# PWMExpander.net
KiCad netlist of a schematic drawn in Altium Designer
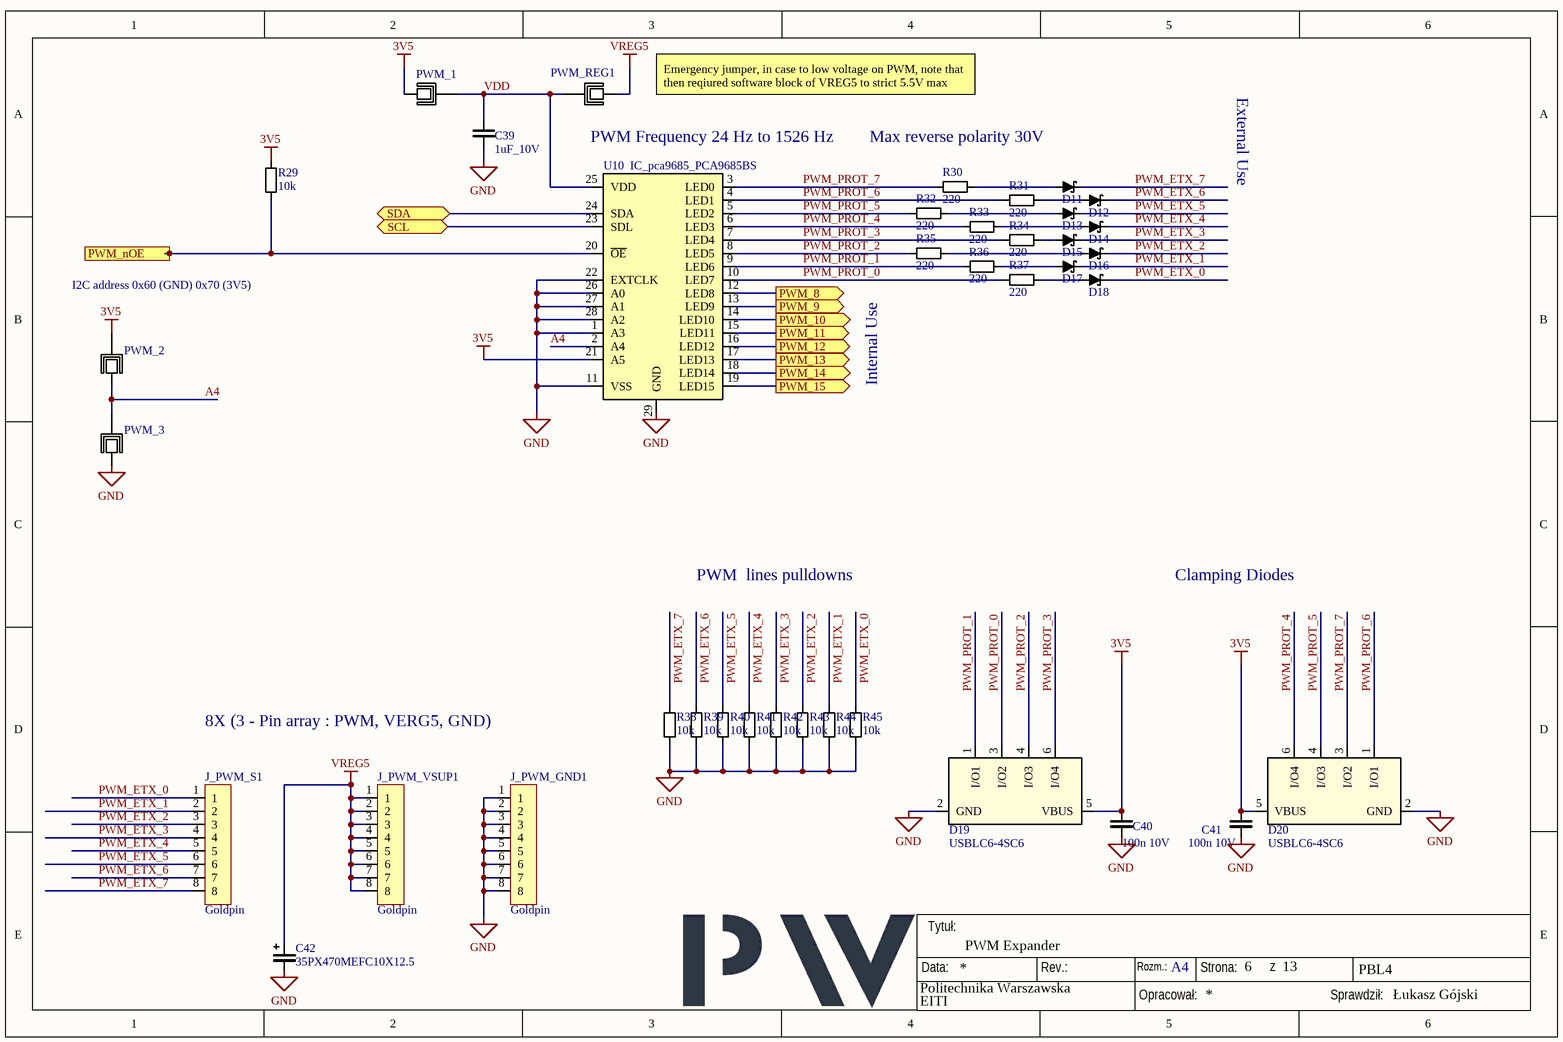
[diagram p0: PWMExpander.SchDoc]

(export (version "E")
  (design (tool "Eeschema 10.0.6"))
  (components
    (comp (ref "C39")
      (value "1uF_10V")
      (footprint "C_0603")
      (description "Ceramic capacitor")
      (fields (field (name "VOLTAGE") "10V") (field (name "TOLERANCE") "10%"))
      (libsource (lib "Common") (part "C_1uF_10V"))
    )
    (comp (ref "C40")
      (value "100n 10V")
      (footprint "C_0603")
      (description "Ceramic capacitor")
      (fields (field (name "VOLTAGE") "10V") (field (name "TOLERANCE") "10%"))
      (libsource (lib "Common") (part "C_100nF_10V"))
    )
    (comp (ref "C41")
      (value "100n 10V")
      (footprint "C_0603")
      (description "Ceramic capacitor")
      (fields (field (name "VOLTAGE") "10V") (field (name "TOLERANCE") "10%"))
      (libsource (lib "Common") (part "C_100nF_10V"))
    )
    (comp (ref "C42")
      (value "35PX470MEFC10X12.5")
      (footprint "CAP_PKPZ_10X12P5_LOW_RUB")
      (description "470 µF 35 V Aluminum Electrolytic Capacitors Radial, Can 2000 Hrs @ 105°C")
      (fields (field (name "VOLTAGE") "35V") (field (name "TOLERANCE") "20%"))
      (libsource (lib "Common") (part "C_Pol_470uF_35V"))
    )
    (comp (ref "D11")
      (value "CUS520,H3F")
      (footprint "SOD2513X115N")
      (description "Schottky Diode 200mA 30V reverse")
      (fields (field (name "POWER") "150mW"))
      (libsource (lib "Common") (part "D schottky 200mA"))
    )
    (comp (ref "D12")
      (value "CUS520,H3F")
      (footprint "SOD2513X115N")
      (description "Schottky Diode 200mA 30V reverse")
      (fields (field (name "POWER") "150mW"))
      (libsource (lib "Common") (part "D schottky 200mA"))
    )
    (comp (ref "D13")
      (value "CUS520,H3F")
      (footprint "SOD2513X115N")
      (description "Schottky Diode 200mA 30V reverse")
      (fields (field (name "POWER") "150mW"))
      (libsource (lib "Common") (part "D schottky 200mA"))
    )
    (comp (ref "D14")
      (value "CUS520,H3F")
      (footprint "SOD2513X115N")
      (description "Schottky Diode 200mA 30V reverse")
      (fields (field (name "POWER") "150mW"))
      (libsource (lib "Common") (part "D schottky 200mA"))
    )
    (comp (ref "D15")
      (value "CUS520,H3F")
      (footprint "SOD2513X115N")
      (description "Schottky Diode 200mA 30V reverse")
      (fields (field (name "POWER") "150mW"))
      (libsource (lib "Common") (part "D schottky 200mA"))
    )
    (comp (ref "D16")
      (value "CUS520,H3F")
      (footprint "SOD2513X115N")
      (description "Schottky Diode 200mA 30V reverse")
      (fields (field (name "POWER") "150mW"))
      (libsource (lib "Common") (part "D schottky 200mA"))
    )
    (comp (ref "D17")
      (value "CUS520,H3F")
      (footprint "SOD2513X115N")
      (description "Schottky Diode 200mA 30V reverse")
      (fields (field (name "POWER") "150mW"))
      (libsource (lib "Common") (part "D schottky 200mA"))
    )
    (comp (ref "D18")
      (value "CUS520,H3F")
      (footprint "SOD2513X115N")
      (description "Schottky Diode 200mA 30V reverse")
      (fields (field (name "POWER") "150mW"))
      (libsource (lib "Common") (part "D schottky 200mA"))
    )
    (comp (ref "D19")
      (value "USBLC6-4SC6")
      (footprint "SOT23-6L_STM")
      (description "Very low capacitance ESD protection")
      (fields (field (name "COPYRIGHT") "Copyright (C) 2025 Ultra Librarian. All rights reserved."))
      (libsource (lib "") (part "USBLC6-4SC6_1"))
    )
    (comp (ref "D20")
      (value "USBLC6-4SC6")
      (footprint "SOT23-6L_STM")
      (description "Very low capacitance ESD protection")
      (fields (field (name "COPYRIGHT") "Copyright (C) 2025 Ultra Librarian. All rights reserved."))
      (libsource (lib "Common") (part "USBLC6-4SC6"))
    )
    (comp (ref "J_PWM_GND1")
      (value "Goldpin")
      (footprint "goldpin8")
      (description "Goldpin Male 8")
      (libsource (lib "Common") (part "Goldpin_array_8"))
    )
    (comp (ref "J_PWM_S1")
      (value "Goldpin")
      (footprint "goldpin8")
      (description "Goldpin Male 8")
      (libsource (lib "Common") (part "Goldpin_array_8"))
    )
    (comp (ref "J_PWM_VSUP1")
      (value "Goldpin")
      (footprint "goldpin8")
      (description "Goldpin Male 8")
      (libsource (lib "Common") (part "Goldpin_array_8"))
    )
    (comp (ref "PWM_1")
      (value "JUMPER")
      (footprint "Jumper")
      (description "Jumper on traces")
      (libsource (lib "Common") (part "Jumper x2"))
    )
    (comp (ref "PWM_2")
      (value "JUMPER")
      (footprint "Jumper")
      (description "Jumper on traces")
      (libsource (lib "Common") (part "Jumper x2"))
    )
    (comp (ref "PWM_3")
      (value "JUMPER")
      (footprint "Jumper")
      (description "Jumper on traces")
      (libsource (lib "Common") (part "Jumper x2"))
    )
    (comp (ref "PWM_REG1")
      (value "JUMPER")
      (footprint "Jumper")
      (description "Jumper on traces")
      (libsource (lib "Common") (part "Jumper x2"))
    )
    (comp (ref "R29")
      (value "10k")
      (footprint "R_0603")
      (description "Resistor")
      (fields (field (name "TOLERANCE") "1%") (field (name "POWER") "100mW"))
      (libsource (lib "Common") (part "R_10k"))
    )
    (comp (ref "R30")
      (value "220")
      (footprint "R_0603")
      (description "Resistor")
      (fields (field (name "TOLERANCE") "1%") (field (name "POWER") "100mW"))
      (libsource (lib "Common") (part "R_220R"))
    )
    (comp (ref "R31")
      (value "220")
      (footprint "R_0603")
      (description "Resistor")
      (fields (field (name "TOLERANCE") "1%") (field (name "POWER") "100mW"))
      (libsource (lib "Common") (part "R_220R"))
    )
    (comp (ref "R32")
      (value "220")
      (footprint "R_0603")
      (description "Resistor")
      (fields (field (name "TOLERANCE") "1%") (field (name "POWER") "100mW"))
      (libsource (lib "Common") (part "R_220R"))
    )
    (comp (ref "R33")
      (value "220")
      (footprint "R_0603")
      (description "Resistor")
      (fields (field (name "TOLERANCE") "1%") (field (name "POWER") "100mW"))
      (libsource (lib "Common") (part "R_220R"))
    )
    (comp (ref "R34")
      (value "220")
      (footprint "R_0603")
      (description "Resistor")
      (fields (field (name "TOLERANCE") "1%") (field (name "POWER") "100mW"))
      (libsource (lib "Common") (part "R_220R"))
    )
    (comp (ref "R35")
      (value "220")
      (footprint "R_0603")
      (description "Resistor")
      (fields (field (name "TOLERANCE") "1%") (field (name "POWER") "100mW"))
      (libsource (lib "Common") (part "R_220R"))
    )
    (comp (ref "R36")
      (value "220")
      (footprint "R_0603")
      (description "Resistor")
      (fields (field (name "TOLERANCE") "1%") (field (name "POWER") "100mW"))
      (libsource (lib "Common") (part "R_220R"))
    )
    (comp (ref "R37")
      (value "220")
      (footprint "R_0603")
      (description "Resistor")
      (fields (field (name "TOLERANCE") "1%") (field (name "POWER") "100mW"))
      (libsource (lib "Common") (part "R_220R"))
    )
    (comp (ref "R38")
      (value "10k")
      (footprint "R_0603")
      (description "Resistor")
      (fields (field (name "TOLERANCE") "1%") (field (name "POWER") "100mW"))
      (libsource (lib "Common") (part "R_10k"))
    )
    (comp (ref "R39")
      (value "10k")
      (footprint "R_0603")
      (description "Resistor")
      (fields (field (name "TOLERANCE") "1%") (field (name "POWER") "100mW"))
      (libsource (lib "Common") (part "R_10k"))
    )
    (comp (ref "R40")
      (value "10k")
      (footprint "R_0603")
      (description "Resistor")
      (fields (field (name "TOLERANCE") "1%") (field (name "POWER") "100mW"))
      (libsource (lib "Common") (part "R_10k"))
    )
    (comp (ref "R41")
      (value "10k")
      (footprint "R_0603")
      (description "Resistor")
      (fields (field (name "TOLERANCE") "1%") (field (name "POWER") "100mW"))
      (libsource (lib "Common") (part "R_10k"))
    )
    (comp (ref "R42")
      (value "10k")
      (footprint "R_0603")
      (description "Resistor")
      (fields (field (name "TOLERANCE") "1%") (field (name "POWER") "100mW"))
      (libsource (lib "Common") (part "R_10k"))
    )
    (comp (ref "R43")
      (value "10k")
      (footprint "R_0603")
      (description "Resistor")
      (fields (field (name "TOLERANCE") "1%") (field (name "POWER") "100mW"))
      (libsource (lib "Common") (part "R_10k"))
    )
    (comp (ref "R44")
      (value "10k")
      (footprint "R_0603")
      (description "Resistor")
      (fields (field (name "TOLERANCE") "1%") (field (name "POWER") "100mW"))
      (libsource (lib "Common") (part "R_10k"))
    )
    (comp (ref "R45")
      (value "10k")
      (footprint "R_0603")
      (description "Resistor")
      (fields (field (name "TOLERANCE") "1%") (field (name "POWER") "100mW"))
      (libsource (lib "Common") (part "R_10k"))
    )
    (comp (ref "U10")
      (value "IC_pca9685_PCA9685BS")
      (footprint "PCA9685_SOT788-1")
      (libsource (lib "IOLib") (part "IC_pca9685_PCA9685BS"))
    )
  )
  (nets
    (net (code "1") (name "/A4") (class "Default")
      (node (ref "PWM_2") (pin "1") (pinfunction "1_1") (pintype "passive"))
      (node (ref "PWM_3") (pin "2") (pinfunction "2_2") (pintype "passive"))
      (node (ref "U10") (pin "2") (pinfunction "A4_2") (pintype "passive"))
    )
    (net (code "2") (name "/PWM_8") (class "Default")
      (node (ref "U10") (pin "12") (pinfunction "LED8_12") (pintype "passive"))
    )
    (net (code "3") (name "/PWM_9") (class "Default")
      (node (ref "U10") (pin "13") (pinfunction "LED9_13") (pintype "passive"))
    )
    (net (code "4") (name "/PWM_10") (class "Default")
      (node (ref "U10") (pin "14") (pinfunction "LED10_14") (pintype "passive"))
    )
    (net (code "5") (name "/PWM_11") (class "Default")
      (node (ref "U10") (pin "15") (pinfunction "LED11_15") (pintype "passive"))
    )
    (net (code "6") (name "/PWM_12") (class "Default")
      (node (ref "U10") (pin "16") (pinfunction "LED12_16") (pintype "passive"))
    )
    (net (code "7") (name "/PWM_13") (class "Default")
      (node (ref "U10") (pin "17") (pinfunction "LED13_17") (pintype "passive"))
    )
    (net (code "8") (name "/PWM_14") (class "Default")
      (node (ref "U10") (pin "18") (pinfunction "LED14_18") (pintype "passive"))
    )
    (net (code "9") (name "/PWM_15") (class "Default")
      (node (ref "U10") (pin "19") (pinfunction "LED15_19") (pintype "passive"))
    )
    (net (code "10") (name "/PWM_ETX_0") (class "Default")
      (node (ref "D18") (pin "K") (pinfunction "K_K") (pintype "passive"))
      (node (ref "J_PWM_S1") (pin "1") (pinfunction "1_1") (pintype "passive"))
      (node (ref "R45") (pin "2") (pinfunction "2_2") (pintype "passive"))
    )
    (net (code "11") (name "/PWM_ETX_1") (class "Default")
      (node (ref "D17") (pin "K") (pinfunction "K_K") (pintype "passive"))
      (node (ref "J_PWM_S1") (pin "2") (pinfunction "2_2") (pintype "passive"))
      (node (ref "R44") (pin "2") (pinfunction "2_2") (pintype "passive"))
    )
    (net (code "12") (name "/PWM_ETX_2") (class "Default")
      (node (ref "D16") (pin "K") (pinfunction "K_K") (pintype "passive"))
      (node (ref "J_PWM_S1") (pin "3") (pinfunction "3_3") (pintype "passive"))
      (node (ref "R43") (pin "2") (pinfunction "2_2") (pintype "passive"))
    )
    (net (code "13") (name "/PWM_ETX_3") (class "Default")
      (node (ref "D15") (pin "K") (pinfunction "K_K") (pintype "passive"))
      (node (ref "J_PWM_S1") (pin "4") (pinfunction "4_4") (pintype "passive"))
      (node (ref "R42") (pin "2") (pinfunction "2_2") (pintype "passive"))
    )
    (net (code "14") (name "/PWM_ETX_4") (class "Default")
      (node (ref "D14") (pin "K") (pinfunction "K_K") (pintype "passive"))
      (node (ref "J_PWM_S1") (pin "5") (pinfunction "5_5") (pintype "passive"))
      (node (ref "R41") (pin "2") (pinfunction "2_2") (pintype "passive"))
    )
    (net (code "15") (name "/PWM_ETX_5") (class "Default")
      (node (ref "D13") (pin "K") (pinfunction "K_K") (pintype "passive"))
      (node (ref "J_PWM_S1") (pin "6") (pinfunction "6_6") (pintype "passive"))
      (node (ref "R40") (pin "2") (pinfunction "2_2") (pintype "passive"))
    )
    (net (code "16") (name "/PWM_ETX_6") (class "Default")
      (node (ref "D12") (pin "K") (pinfunction "K_K") (pintype "passive"))
      (node (ref "J_PWM_S1") (pin "7") (pinfunction "7_7") (pintype "passive"))
      (node (ref "R39") (pin "2") (pinfunction "2_2") (pintype "passive"))
    )
    (net (code "17") (name "/PWM_ETX_7") (class "Default")
      (node (ref "D11") (pin "K") (pinfunction "K_K") (pintype "passive"))
      (node (ref "J_PWM_S1") (pin "8") (pinfunction "8_8") (pintype "passive"))
      (node (ref "R38") (pin "2") (pinfunction "2_2") (pintype "passive"))
    )
    (net (code "18") (name "/PWM_PROT_0") (class "Default")
      (node (ref "D19") (pin "3") (pinfunction "I/O2_3") (pintype "passive"))
      (node (ref "R37") (pin "1") (pinfunction "1_1") (pintype "passive"))
      (node (ref "U10") (pin "10") (pinfunction "LED7_10") (pintype "passive"))
    )
    (net (code "19") (name "/PWM_PROT_1") (class "Default")
      (node (ref "D19") (pin "1") (pinfunction "I/O1_1") (pintype "passive"))
      (node (ref "R36") (pin "1") (pinfunction "1_1") (pintype "passive"))
      (node (ref "U10") (pin "9") (pinfunction "LED6_9") (pintype "passive"))
    )
    (net (code "20") (name "/PWM_PROT_2") (class "Default")
      (node (ref "D19") (pin "4") (pinfunction "I/O3_4") (pintype "passive"))
      (node (ref "R35") (pin "1") (pinfunction "1_1") (pintype "passive"))
      (node (ref "U10") (pin "8") (pinfunction "LED5_8") (pintype "passive"))
    )
    (net (code "21") (name "/PWM_PROT_3") (class "Default")
      (node (ref "D19") (pin "6") (pinfunction "I/O4_6") (pintype "passive"))
      (node (ref "R34") (pin "1") (pinfunction "1_1") (pintype "passive"))
      (node (ref "U10") (pin "7") (pinfunction "LED4_7") (pintype "passive"))
    )
    (net (code "22") (name "/PWM_PROT_4") (class "Default")
      (node (ref "D20") (pin "6") (pinfunction "I/O4_6") (pintype "passive"))
      (node (ref "R33") (pin "1") (pinfunction "1_1") (pintype "passive"))
      (node (ref "U10") (pin "6") (pinfunction "LED3_6") (pintype "passive"))
    )
    (net (code "23") (name "/PWM_PROT_5") (class "Default")
      (node (ref "D20") (pin "4") (pinfunction "I/O3_4") (pintype "passive"))
      (node (ref "R32") (pin "1") (pinfunction "1_1") (pintype "passive"))
      (node (ref "U10") (pin "5") (pinfunction "LED2_5") (pintype "passive"))
    )
    (net (code "24") (name "/PWM_PROT_6") (class "Default")
      (node (ref "D20") (pin "1") (pinfunction "I/O1_1") (pintype "passive"))
      (node (ref "R31") (pin "1") (pinfunction "1_1") (pintype "passive"))
      (node (ref "U10") (pin "4") (pinfunction "LED1_4") (pintype "passive"))
    )
    (net (code "25") (name "/PWM_PROT_7") (class "Default")
      (node (ref "D20") (pin "3") (pinfunction "I/O2_3") (pintype "passive"))
      (node (ref "R30") (pin "1") (pinfunction "1_1") (pintype "passive"))
      (node (ref "U10") (pin "3") (pinfunction "LED0_3") (pintype "passive"))
    )
    (net (code "26") (name "/PWM_nOE") (class "Default")
      (node (ref "R29") (pin "1") (pinfunction "1_1") (pintype "passive"))
      (node (ref "U10") (pin "20") (pinfunction "~{OE}_20") (pintype "passive"))
    )
    (net (code "27") (name "/SCL") (class "Default")
      (node (ref "U10") (pin "23") (pinfunction "SDL_23") (pintype "passive"))
    )
    (net (code "28") (name "/SDA") (class "Default")
      (node (ref "U10") (pin "24") (pinfunction "SDA_24") (pintype "passive"))
    )
    (net (code "29") (name "/VDD") (class "Default")
      (node (ref "C39") (pin "2") (pinfunction "2_2") (pintype "passive"))
      (node (ref "PWM_1") (pin "2") (pinfunction "2_2") (pintype "passive"))
      (node (ref "PWM_REG1") (pin "2") (pinfunction "2_2") (pintype "passive"))
      (node (ref "U10") (pin "25") (pinfunction "VDD_25") (pintype "passive"))
    )
    (net (code "30") (name "3V5") (class "Default")
      (node (ref "C40") (pin "2") (pinfunction "2_2") (pintype "passive"))
      (node (ref "C41") (pin "2") (pinfunction "2_2") (pintype "passive"))
      (node (ref "D19") (pin "5") (pinfunction "VBUS_5") (pintype "passive"))
      (node (ref "D20") (pin "5") (pinfunction "VBUS_5") (pintype "passive"))
      (node (ref "PWM_1") (pin "1") (pinfunction "1_1") (pintype "passive"))
      (node (ref "PWM_2") (pin "2") (pinfunction "2_2") (pintype "passive"))
      (node (ref "R29") (pin "2") (pinfunction "2_2") (pintype "passive"))
      (node (ref "U10") (pin "21") (pinfunction "A5_21") (pintype "passive"))
    )
    (net (code "31") (name "GND") (class "Default")
      (node (ref "C39") (pin "1") (pinfunction "1_1") (pintype "passive"))
      (node (ref "C40") (pin "1") (pinfunction "1_1") (pintype "passive"))
      (node (ref "C41") (pin "1") (pinfunction "1_1") (pintype "passive"))
      (node (ref "C42") (pin "2") (pinfunction "2_2") (pintype "passive"))
      (node (ref "D19") (pin "2") (pinfunction "GND_2") (pintype "passive"))
      (node (ref "D20") (pin "2") (pinfunction "GND_2") (pintype "passive"))
      (node (ref "J_PWM_GND1") (pin "1") (pinfunction "1_1") (pintype "passive"))
      (node (ref "J_PWM_GND1") (pin "2") (pinfunction "2_2") (pintype "passive"))
      (node (ref "J_PWM_GND1") (pin "3") (pinfunction "3_3") (pintype "passive"))
      (node (ref "J_PWM_GND1") (pin "4") (pinfunction "4_4") (pintype "passive"))
      (node (ref "J_PWM_GND1") (pin "5") (pinfunction "5_5") (pintype "passive"))
      (node (ref "J_PWM_GND1") (pin "6") (pinfunction "6_6") (pintype "passive"))
      (node (ref "J_PWM_GND1") (pin "7") (pinfunction "7_7") (pintype "passive"))
      (node (ref "J_PWM_GND1") (pin "8") (pinfunction "8_8") (pintype "passive"))
      (node (ref "PWM_3") (pin "1") (pinfunction "1_1") (pintype "passive"))
      (node (ref "R38") (pin "1") (pinfunction "1_1") (pintype "passive"))
      (node (ref "R39") (pin "1") (pinfunction "1_1") (pintype "passive"))
      (node (ref "R40") (pin "1") (pinfunction "1_1") (pintype "passive"))
      (node (ref "R41") (pin "1") (pinfunction "1_1") (pintype "passive"))
      (node (ref "R42") (pin "1") (pinfunction "1_1") (pintype "passive"))
      (node (ref "R43") (pin "1") (pinfunction "1_1") (pintype "passive"))
      (node (ref "R44") (pin "1") (pinfunction "1_1") (pintype "passive"))
      (node (ref "R45") (pin "1") (pinfunction "1_1") (pintype "passive"))
      (node (ref "U10") (pin "1") (pinfunction "A3_1") (pintype "passive"))
      (node (ref "U10") (pin "11") (pinfunction "VSS_11") (pintype "passive"))
      (node (ref "U10") (pin "22") (pinfunction "EXTCLK_22") (pintype "passive"))
      (node (ref "U10") (pin "26") (pinfunction "A0_26") (pintype "passive"))
      (node (ref "U10") (pin "27") (pinfunction "A1_27") (pintype "passive"))
      (node (ref "U10") (pin "28") (pinfunction "A2_28") (pintype "passive"))
      (node (ref "U10") (pin "29") (pinfunction "GND_29") (pintype "passive"))
    )
    (net (code "32") (name "Net-(D11-PadA)") (class "Default")
      (node (ref "D11") (pin "A") (pinfunction "A_A") (pintype "passive"))
      (node (ref "R30") (pin "2") (pinfunction "2_2") (pintype "passive"))
    )
    (net (code "33") (name "Net-(D12-PadA)") (class "Default")
      (node (ref "D12") (pin "A") (pinfunction "A_A") (pintype "passive"))
      (node (ref "R31") (pin "2") (pinfunction "2_2") (pintype "passive"))
    )
    (net (code "34") (name "Net-(D13-PadA)") (class "Default")
      (node (ref "D13") (pin "A") (pinfunction "A_A") (pintype "passive"))
      (node (ref "R32") (pin "2") (pinfunction "2_2") (pintype "passive"))
    )
    (net (code "35") (name "Net-(D14-PadA)") (class "Default")
      (node (ref "D14") (pin "A") (pinfunction "A_A") (pintype "passive"))
      (node (ref "R33") (pin "2") (pinfunction "2_2") (pintype "passive"))
    )
    (net (code "36") (name "Net-(D15-PadA)") (class "Default")
      (node (ref "D15") (pin "A") (pinfunction "A_A") (pintype "passive"))
      (node (ref "R34") (pin "2") (pinfunction "2_2") (pintype "passive"))
    )
    (net (code "37") (name "Net-(D16-PadA)") (class "Default")
      (node (ref "D16") (pin "A") (pinfunction "A_A") (pintype "passive"))
      (node (ref "R35") (pin "2") (pinfunction "2_2") (pintype "passive"))
    )
    (net (code "38") (name "Net-(D17-PadA)") (class "Default")
      (node (ref "D17") (pin "A") (pinfunction "A_A") (pintype "passive"))
      (node (ref "R36") (pin "2") (pinfunction "2_2") (pintype "passive"))
    )
    (net (code "39") (name "Net-(D18-PadA)") (class "Default")
      (node (ref "D18") (pin "A") (pinfunction "A_A") (pintype "passive"))
      (node (ref "R37") (pin "2") (pinfunction "2_2") (pintype "passive"))
    )
    (net (code "40") (name "VREG5") (class "Default")
      (node (ref "C42") (pin "1") (pinfunction "1_1") (pintype "passive"))
      (node (ref "J_PWM_VSUP1") (pin "1") (pinfunction "1_1") (pintype "passive"))
      (node (ref "J_PWM_VSUP1") (pin "2") (pinfunction "2_2") (pintype "passive"))
      (node (ref "J_PWM_VSUP1") (pin "3") (pinfunction "3_3") (pintype "passive"))
      (node (ref "J_PWM_VSUP1") (pin "4") (pinfunction "4_4") (pintype "passive"))
      (node (ref "J_PWM_VSUP1") (pin "5") (pinfunction "5_5") (pintype "passive"))
      (node (ref "J_PWM_VSUP1") (pin "6") (pinfunction "6_6") (pintype "passive"))
      (node (ref "J_PWM_VSUP1") (pin "7") (pinfunction "7_7") (pintype "passive"))
      (node (ref "J_PWM_VSUP1") (pin "8") (pinfunction "8_8") (pintype "passive"))
      (node (ref "PWM_REG1") (pin "1") (pinfunction "1_1") (pintype "passive"))
    )
  )
)
